# Motor_Board.net
KiCad netlist of a schematic drawn in EAGLE
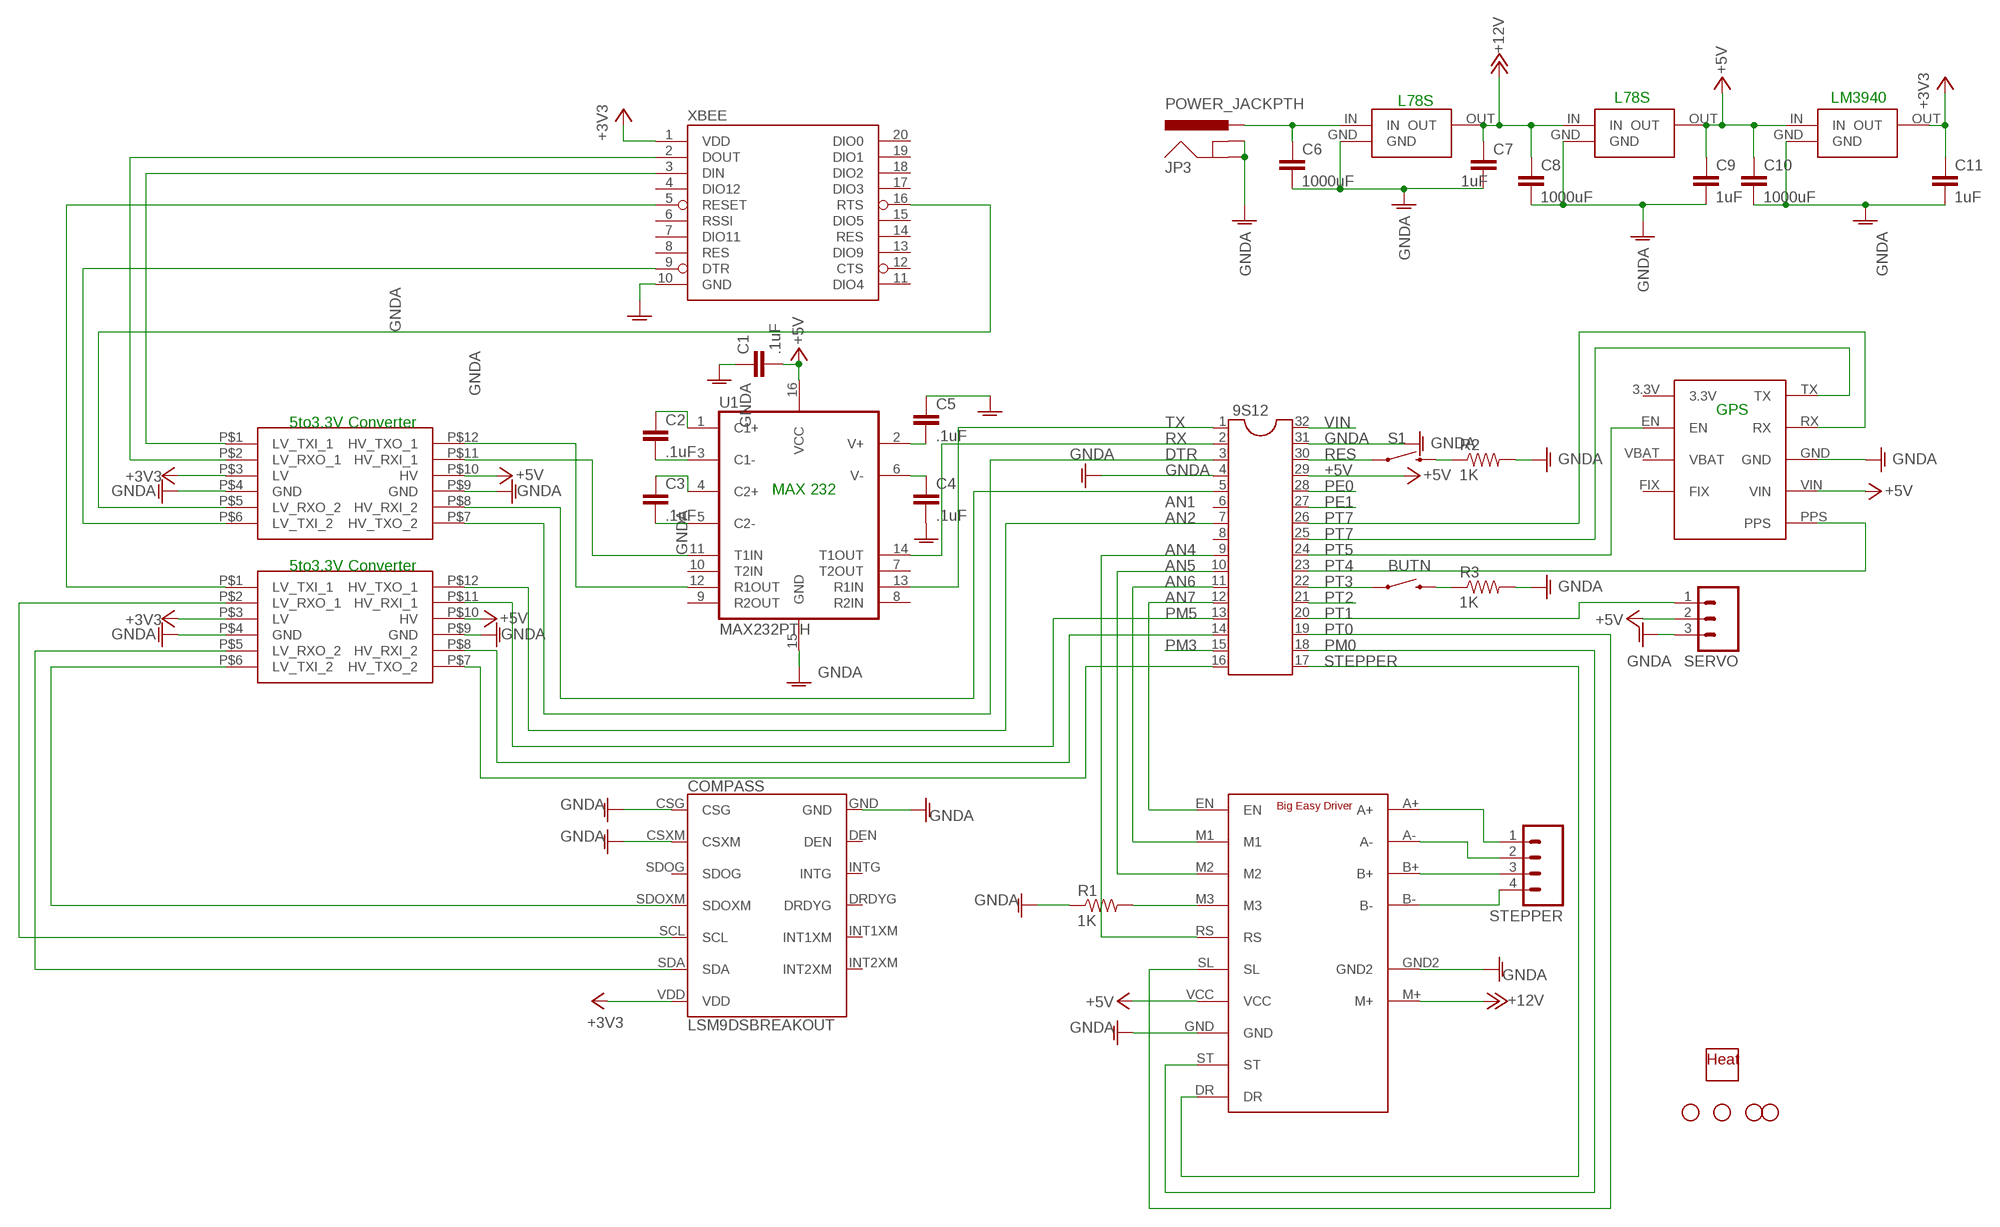
[diagram p0: schematic, sheet 1]

(export (version "E")
  (design (tool "Eeschema 10.0.6"))
  (components
    (comp (ref "9S12")
      (value "DIL32")
      (footprint "eagle-import:DIL32")
      (libsource (lib "eagle-import") (part "DIL32"))
    )
    (comp (ref "BUTN")
      (value "EXTERNALBUTTON")
      (footprint "eagle-import:EXTERNALBUTTON")
      (libsource (lib "eagle-import") (part "EXTERNALBUTTON"))
    )
    (comp (ref "C1")
      (value ".1uF")
      (footprint "eagle-import:CAP-PTH-SMALL")
      (libsource (lib "eagle-import") (part "CAPPTH"))
    )
    (comp (ref "C2")
      (value ".1uF")
      (footprint "eagle-import:CAP-PTH-SMALL")
      (libsource (lib "eagle-import") (part "CAPPTH"))
    )
    (comp (ref "C3")
      (value ".1uF")
      (footprint "eagle-import:CAP-PTH-SMALL")
      (libsource (lib "eagle-import") (part "CAPPTH"))
    )
    (comp (ref "C4")
      (value ".1uF")
      (footprint "eagle-import:CAP-PTH-SMALL")
      (libsource (lib "eagle-import") (part "CAPPTH"))
    )
    (comp (ref "C5")
      (value ".1uF")
      (footprint "eagle-import:CAP-PTH-SMALL")
      (libsource (lib "eagle-import") (part "CAPPTH"))
    )
    (comp (ref "C6")
      (value "1000uF")
      (footprint "eagle-import:CAP")
      (libsource (lib "eagle-import") (part "CAP_2000UF"))
    )
    (comp (ref "C7")
      (value "1uF")
      (footprint "eagle-import:CAP-PTH-SMALL")
      (libsource (lib "eagle-import") (part "CAPPTH"))
    )
    (comp (ref "C8")
      (value "1000uF")
      (footprint "eagle-import:CAP")
      (libsource (lib "eagle-import") (part "CAP_2000UF"))
    )
    (comp (ref "C9")
      (value "1uF")
      (footprint "eagle-import:CAP-PTH-SMALL")
      (libsource (lib "eagle-import") (part "CAPPTH"))
    )
    (comp (ref "C10")
      (value "1000uF")
      (footprint "eagle-import:CAP")
      (libsource (lib "eagle-import") (part "CAP_2000UF"))
    )
    (comp (ref "C11")
      (value "1uF")
      (footprint "eagle-import:CAP-PTH-SMALL")
      (libsource (lib "eagle-import") (part "CAPPTH"))
    )
    (comp (ref "COMPASS")
      (value "LSM9DSBREAKOUT")
      (footprint "eagle-import:IMUBREAKOUT")
      (libsource (lib "eagle-import") (part "LSM9DSBREAKOUT"))
    )
    (comp (ref "JP3")
      (value "POWER_JACKPTH")
      (footprint "eagle-import:POWER_JACK_PTH")
      (libsource (lib "eagle-import") (part "POWER_JACKPTH"))
    )
    (comp (ref "R1")
      (value "1K")
      (footprint "eagle-import:AXIAL-0.4")
      (libsource (lib "eagle-import") (part "RESISTORPTH-1/4W"))
    )
    (comp (ref "R2")
      (value "1K")
      (footprint "eagle-import:AXIAL-0.4")
      (libsource (lib "eagle-import") (part "RESISTORPTH-1/4W"))
    )
    (comp (ref "R3")
      (value "1K")
      (footprint "eagle-import:AXIAL-0.4")
      (libsource (lib "eagle-import") (part "RESISTORPTH-1/4W"))
    )
    (comp (ref "REG_5TO3.3")
      (value "POWERREG_5TO3.3_NOHEAT")
      (footprint "eagle-import:POWERREG_NOHEAT")
      (libsource (lib "eagle-import") (part "POWERREG_5TO3.3_NOHEAT"))
    )
    (comp (ref "REG_12TO5")
      (value "POWERREG_12TO5")
      (footprint "eagle-import:POWERREG")
      (libsource (lib "eagle-import") (part "POWERREG_12TO5"))
    )
    (comp (ref "REG_18TO12")
      (value "POWERREG18VTO12V")
      (footprint "eagle-import:POWERREG")
      (libsource (lib "eagle-import") (part "POWERREG18VTO12V"))
    )
    (comp (ref "S1")
      (value "SWITCH-MOMENTARY-2PTH")
      (footprint "eagle-import:TACTILE-PTH")
      (libsource (lib "eagle-import") (part "SWITCH-MOMENTARY-2PTH"))
    )
    (comp (ref "SERVO")
      (value "M03PTH")
      (footprint "eagle-import:1X03")
      (libsource (lib "eagle-import") (part "M03PTH"))
    )
    (comp (ref "STANDOFF1")
      (value "STAND-OFF")
      (footprint "eagle-import:STAND-OFF")
      (libsource (lib "eagle-import") (part "STAND-OFF"))
    )
    (comp (ref "STANDOFF2")
      (value "STAND-OFF")
      (footprint "eagle-import:STAND-OFF")
      (libsource (lib "eagle-import") (part "STAND-OFF"))
    )
    (comp (ref "STANDOFF3")
      (value "STAND-OFF")
      (footprint "eagle-import:STAND-OFF")
      (libsource (lib "eagle-import") (part "STAND-OFF"))
    )
    (comp (ref "STANDOFF4")
      (value "STAND-OFF")
      (footprint "eagle-import:STAND-OFF")
      (libsource (lib "eagle-import") (part "STAND-OFF"))
    )
    (comp (ref "STEPPER")
      (value "M04NO_SILK_ALL_ROUND")
      (footprint "eagle-import:1X04_NO_SILK_ALL_ROUND")
      (libsource (lib "eagle-import") (part "M04NO_SILK_ALL_ROUND"))
    )
    (comp (ref "U$1")
      (value "5to3.3")
      (footprint "eagle-import:LOGIC_LEVEL_CONVERTER")
      (libsource (lib "eagle-import") (part "LOGIC_LEVEL_CONVERTER"))
    )
    (comp (ref "U$2")
      (value "5to3.3")
      (footprint "eagle-import:LOGIC_LEVEL_CONVERTER")
      (libsource (lib "eagle-import") (part "LOGIC_LEVEL_CONVERTER"))
    )
    (comp (ref "U$3")
      (value "BIGEASYDRIVER")
      (footprint "eagle-import:BIGEASYDRIVER")
      (libsource (lib "eagle-import") (part "BIGEASYDRIVER"))
    )
    (comp (ref "U$4")
      (value "GPS")
      (footprint "eagle-import:GPS")
      (libsource (lib "eagle-import") (part "GPS"))
    )
    (comp (ref "U$9")
      (value "HEATSINK")
      (footprint "eagle-import:HEATSINK")
      (libsource (lib "eagle-import") (part "HEATSINK"))
    )
    (comp (ref "U1")
      (value "MAX232PTH")
      (footprint "eagle-import:DIL16")
      (libsource (lib "eagle-import") (part "MAX232PTH"))
    )
    (comp (ref "XBEE")
      (value "XBEE-1B1")
      (footprint "eagle-import:XBEE-1")
      (libsource (lib "eagle-import") (part "XBEE-1B1"))
    )
  )
  (nets
    (net (code "1") (name "+3V3") (class "Default")
      (node (ref "C11") (pin "1") (pinfunction "1_1") (pintype "passive"))
      (node (ref "COMPASS") (pin "VDD") (pinfunction "VDD_VDD") (pintype "bidirectional"))
      (node (ref "REG_5TO3.3") (pin "OUT") (pinfunction "OUT_OUT") (pintype "bidirectional"))
      (node (ref "U$1") (pin "P$3") (pinfunction "LV_P$3") (pintype "bidirectional"))
      (node (ref "U$2") (pin "P$3") (pinfunction "LV_P$3") (pintype "bidirectional"))
      (node (ref "XBEE") (pin "1") (pinfunction "VDD_1") (pintype "power_in"))
    )
    (net (code "2") (name "+5V") (class "Default")
      (node (ref "9S12") (pin "29") (pinfunction "29_29") (pintype "passive"))
      (node (ref "C1") (pin "2") (pinfunction "2_2") (pintype "passive"))
      (node (ref "C10") (pin "1") (pinfunction "1_1") (pintype "passive"))
      (node (ref "C9") (pin "1") (pinfunction "1_1") (pintype "passive"))
      (node (ref "REG_12TO5") (pin "OUT") (pinfunction "OUT_OUT") (pintype "bidirectional"))
      (node (ref "REG_5TO3.3") (pin "IN") (pinfunction "IN_IN") (pintype "bidirectional"))
      (node (ref "SERVO") (pin "2") (pinfunction "2_2") (pintype "passive"))
      (node (ref "U$1") (pin "P$10") (pinfunction "HV_P$10") (pintype "bidirectional"))
      (node (ref "U$2") (pin "P$10") (pinfunction "HV_P$10") (pintype "bidirectional"))
      (node (ref "U$3") (pin "VCC") (pinfunction "VCC_VCC") (pintype "bidirectional"))
      (node (ref "U$4") (pin "VIN") (pinfunction "VIN_VIN") (pintype "bidirectional"))
      (node (ref "U1") (pin "16") (pinfunction "VCC_16") (pintype "bidirectional"))
    )
    (net (code "3") (name "+12V") (class "Default")
      (node (ref "C7") (pin "1") (pinfunction "1_1") (pintype "passive"))
      (node (ref "C8") (pin "1") (pinfunction "1_1") (pintype "passive"))
      (node (ref "REG_12TO5") (pin "IN") (pinfunction "IN_IN") (pintype "bidirectional"))
      (node (ref "REG_18TO12") (pin "OUT") (pinfunction "OUT_OUT") (pintype "bidirectional"))
      (node (ref "U$3") (pin "M+") (pinfunction "M+_M+") (pintype "bidirectional"))
    )
    (net (code "4") (name "/AN1") (class "Default")
      (node (ref "U$2") (pin "P$6") (pinfunction "LV_TXI_2_P$6") (pintype "bidirectional"))
      (node (ref "XBEE") (pin "9") (pinfunction "DTR_9") (pintype "bidirectional"))
    )
    (net (code "5") (name "/AN2") (class "Default")
      (node (ref "U$1") (pin "P$1") (pinfunction "LV_TXI_1_P$1") (pintype "bidirectional"))
      (node (ref "XBEE") (pin "5") (pinfunction "RESET_5") (pintype "input"))
    )
    (net (code "6") (name "/AN4") (class "Default")
      (node (ref "9S12") (pin "9") (pinfunction "9_9") (pintype "passive"))
      (node (ref "U$3") (pin "RS") (pinfunction "RS_RS") (pintype "bidirectional"))
    )
    (net (code "7") (name "/AN5") (class "Default")
      (node (ref "9S12") (pin "10") (pinfunction "10_10") (pintype "passive"))
      (node (ref "U$3") (pin "M2") (pinfunction "M2_M2") (pintype "bidirectional"))
    )
    (net (code "8") (name "/AN6") (class "Default")
      (node (ref "9S12") (pin "11") (pinfunction "11_11") (pintype "passive"))
      (node (ref "U$3") (pin "M1") (pinfunction "M1_M1") (pintype "bidirectional"))
    )
    (net (code "9") (name "/AN7") (class "Default")
      (node (ref "9S12") (pin "12") (pinfunction "12_12") (pintype "passive"))
      (node (ref "U$3") (pin "EN") (pinfunction "EN_EN") (pintype "bidirectional"))
    )
    (net (code "10") (name "/DTR") (class "Default")
      (node (ref "9S12") (pin "3") (pinfunction "3_3") (pintype "passive"))
      (node (ref "U$2") (pin "P$7") (pinfunction "HV_TXO_2_P$7") (pintype "bidirectional"))
    )
    (net (code "11") (name "/PE0") (class "Default")
      (node (ref "9S12") (pin "28") (pinfunction "28_28") (pintype "passive"))
    )
    (net (code "12") (name "/PE1") (class "Default")
      (node (ref "9S12") (pin "27") (pinfunction "27_27") (pintype "passive"))
    )
    (net (code "13") (name "/PM0") (class "Default")
      (node (ref "9S12") (pin "18") (pinfunction "18_18") (pintype "passive"))
      (node (ref "U$3") (pin "ST") (pinfunction "ST_ST") (pintype "bidirectional"))
    )
    (net (code "14") (name "/PM3") (class "Default")
      (node (ref "9S12") (pin "15") (pinfunction "15_15") (pintype "passive"))
    )
    (net (code "15") (name "/PM5") (class "Default")
      (node (ref "9S12") (pin "13") (pinfunction "13_13") (pintype "passive"))
      (node (ref "U$1") (pin "P$11") (pinfunction "HV_RXI_1_P$11") (pintype "bidirectional"))
    )
    (net (code "16") (name "/PT0") (class "Default")
      (node (ref "9S12") (pin "19") (pinfunction "19_19") (pintype "passive"))
      (node (ref "U$3") (pin "SL") (pinfunction "SL_SL") (pintype "bidirectional"))
    )
    (net (code "17") (name "/PT1") (class "Default")
      (node (ref "9S12") (pin "20") (pinfunction "20_20") (pintype "passive"))
      (node (ref "SERVO") (pin "1") (pinfunction "1_1") (pintype "passive"))
    )
    (net (code "18") (name "/PT2") (class "Default")
      (node (ref "9S12") (pin "21") (pinfunction "21_21") (pintype "passive"))
    )
    (net (code "19") (name "/PT3") (class "Default")
      (node (ref "9S12") (pin "22") (pinfunction "22_22") (pintype "passive"))
      (node (ref "BUTN") (pin "1") (pinfunction "1_1") (pintype "passive"))
    )
    (net (code "20") (name "/PT4") (class "Default")
      (node (ref "9S12") (pin "23") (pinfunction "23_23") (pintype "passive"))
      (node (ref "U$4") (pin "PPS") (pinfunction "PPS_PPS") (pintype "bidirectional"))
    )
    (net (code "21") (name "/PT5") (class "Default")
      (node (ref "9S12") (pin "24") (pinfunction "24_24") (pintype "passive"))
      (node (ref "U$4") (pin "EN") (pinfunction "EN_EN") (pintype "bidirectional"))
    )
    (net (code "22") (name "/PT7") (class "Default")
      (node (ref "9S12") (pin "26") (pinfunction "26_26") (pintype "passive"))
      (node (ref "U$4") (pin "RX") (pinfunction "RX_RX") (pintype "bidirectional"))
    )
    (net (code "23") (name "/RES") (class "Default")
      (node (ref "9S12") (pin "30") (pinfunction "30_30") (pintype "passive"))
      (node (ref "S1") (pin "1") (pinfunction "1_1") (pintype "passive"))
    )
    (net (code "24") (name "/RX") (class "Default")
      (node (ref "U$2") (pin "P$2") (pinfunction "LV_RXO_1_P$2") (pintype "bidirectional"))
      (node (ref "XBEE") (pin "2") (pinfunction "DOUT_2") (pintype "output"))
    )
    (net (code "25") (name "/STEPPER") (class "Default")
      (node (ref "9S12") (pin "17") (pinfunction "17_17") (pintype "passive"))
      (node (ref "U$3") (pin "DR") (pinfunction "DR_DR") (pintype "bidirectional"))
    )
    (net (code "26") (name "/TX") (class "Default")
      (node (ref "U$2") (pin "P$1") (pinfunction "LV_TXI_1_P$1") (pintype "bidirectional"))
      (node (ref "XBEE") (pin "3") (pinfunction "DIN_3") (pintype "input"))
    )
    (net (code "27") (name "/VIN") (class "Default")
      (node (ref "9S12") (pin "32") (pinfunction "32_32") (pintype "passive"))
    )
    (net (code "28") (name "GNDA") (class "Default")
      (node (ref "9S12") (pin "31") (pinfunction "31_31") (pintype "passive"))
      (node (ref "9S12") (pin "4") (pinfunction "4_4") (pintype "passive"))
      (node (ref "C1") (pin "1") (pinfunction "1_1") (pintype "passive"))
      (node (ref "C10") (pin "2") (pinfunction "2_2") (pintype "passive"))
      (node (ref "C11") (pin "2") (pinfunction "2_2") (pintype "passive"))
      (node (ref "C4") (pin "2") (pinfunction "2_2") (pintype "passive"))
      (node (ref "C5") (pin "1") (pinfunction "1_1") (pintype "passive"))
      (node (ref "C6") (pin "2") (pinfunction "2_2") (pintype "passive"))
      (node (ref "C7") (pin "2") (pinfunction "2_2") (pintype "passive"))
      (node (ref "C8") (pin "2") (pinfunction "2_2") (pintype "passive"))
      (node (ref "C9") (pin "2") (pinfunction "2_2") (pintype "passive"))
      (node (ref "COMPASS") (pin "CSG") (pinfunction "CSG_CSG") (pintype "bidirectional"))
      (node (ref "COMPASS") (pin "CSXM") (pinfunction "CSXM_CSXM") (pintype "bidirectional"))
      (node (ref "COMPASS") (pin "GND") (pinfunction "GND_GND") (pintype "bidirectional"))
      (node (ref "JP3") (pin "GND") (pinfunction "GND_GND") (pintype "bidirectional"))
      (node (ref "JP3") (pin "GNDBREAK") (pinfunction "GNDBREAK_GNDBREAK") (pintype "bidirectional"))
      (node (ref "R1") (pin "P$1") (pinfunction "1_P$1") (pintype "passive"))
      (node (ref "R2") (pin "P$2") (pinfunction "2_P$2") (pintype "passive"))
      (node (ref "R3") (pin "P$2") (pinfunction "2_P$2") (pintype "passive"))
      (node (ref "REG_12TO5") (pin "GND") (pinfunction "GND_GND") (pintype "bidirectional"))
      (node (ref "REG_18TO12") (pin "GND") (pinfunction "GND_GND") (pintype "bidirectional"))
      (node (ref "REG_5TO3.3") (pin "GND") (pinfunction "GND_GND") (pintype "bidirectional"))
      (node (ref "SERVO") (pin "3") (pinfunction "3_3") (pintype "passive"))
      (node (ref "U$1") (pin "P$4") (pinfunction "GND_P$4") (pintype "bidirectional"))
      (node (ref "U$1") (pin "P$9") (pinfunction "GND_P$9") (pintype "bidirectional"))
      (node (ref "U$2") (pin "P$4") (pinfunction "GND_P$4") (pintype "bidirectional"))
      (node (ref "U$2") (pin "P$9") (pinfunction "GND_P$9") (pintype "bidirectional"))
      (node (ref "U$3") (pin "GND") (pinfunction "GND_GND") (pintype "bidirectional"))
      (node (ref "U$3") (pin "GND2") (pinfunction "GND2_GND2") (pintype "bidirectional"))
      (node (ref "U$4") (pin "GND") (pinfunction "GND_GND") (pintype "bidirectional"))
      (node (ref "U1") (pin "15") (pinfunction "GND_15") (pintype "bidirectional"))
      (node (ref "XBEE") (pin "10") (pinfunction "GND_10") (pintype "power_in"))
    )
    (net (code "29") (name "Net-(9S12-Pad25)") (class "Default")
      (node (ref "9S12") (pin "25") (pinfunction "25_25") (pintype "passive"))
      (node (ref "U$4") (pin "TX") (pinfunction "TX_TX") (pintype "bidirectional"))
    )
    (net (code "30") (name "Net-(C6-Pad1)") (class "Default")
      (node (ref "C6") (pin "1") (pinfunction "1_1") (pintype "passive"))
      (node (ref "JP3") (pin "PWR") (pinfunction "PWR_PWR") (pintype "bidirectional"))
      (node (ref "REG_18TO12") (pin "IN") (pinfunction "IN_IN") (pintype "bidirectional"))
    )
    (net (code "31") (name "Net-(R1-2)") (class "Default")
      (node (ref "R1") (pin "P$2") (pinfunction "2_P$2") (pintype "passive"))
      (node (ref "U$3") (pin "M3") (pinfunction "M3_M3") (pintype "bidirectional"))
    )
    (net (code "32") (name "Net-(R2-1)") (class "Default")
      (node (ref "R2") (pin "P$1") (pinfunction "1_P$1") (pintype "passive"))
      (node (ref "S1") (pin "3") (pinfunction "2_3") (pintype "passive"))
    )
    (net (code "33") (name "Net-(R3-1)") (class "Default")
      (node (ref "BUTN") (pin "2") (pinfunction "2_2") (pintype "passive"))
      (node (ref "R3") (pin "P$1") (pinfunction "1_P$1") (pintype "passive"))
    )
    (net (code "34") (name "Net-(STEPPER-Pad1)") (class "Default")
      (node (ref "STEPPER") (pin "1") (pinfunction "1_1") (pintype "passive"))
      (node (ref "U$3") (pin "A+") (pinfunction "A+_A+") (pintype "bidirectional"))
    )
    (net (code "35") (name "Net-(STEPPER-Pad2)") (class "Default")
      (node (ref "STEPPER") (pin "2") (pinfunction "2_2") (pintype "passive"))
      (node (ref "U$3") (pin "A-") (pinfunction "A-_A-") (pintype "bidirectional"))
    )
    (net (code "36") (name "Net-(STEPPER-Pad3)") (class "Default")
      (node (ref "STEPPER") (pin "3") (pinfunction "3_3") (pintype "passive"))
      (node (ref "U$3") (pin "B+") (pinfunction "B+_B+") (pintype "bidirectional"))
    )
    (net (code "37") (name "Net-(STEPPER-Pad4)") (class "Default")
      (node (ref "STEPPER") (pin "4") (pinfunction "4_4") (pintype "passive"))
      (node (ref "U$3") (pin "B-") (pinfunction "B-_B-") (pintype "bidirectional"))
    )
    (net (code "38") (name "Net-(U$1-HV_RXI_2)") (class "Default")
      (node (ref "9S12") (pin "14") (pinfunction "14_14") (pintype "passive"))
      (node (ref "U$1") (pin "P$8") (pinfunction "HV_RXI_2_P$8") (pintype "bidirectional"))
    )
    (net (code "39") (name "Net-(U$1-HV_TXO_1)") (class "Default")
      (node (ref "9S12") (pin "7") (pinfunction "7_7") (pintype "passive"))
      (node (ref "U$1") (pin "P$12") (pinfunction "HV_TXO_1_P$12") (pintype "bidirectional"))
    )
    (net (code "40") (name "Net-(U$1-HV_TXO_2)") (class "Default")
      (node (ref "9S12") (pin "16") (pinfunction "16_16") (pintype "passive"))
      (node (ref "U$1") (pin "P$7") (pinfunction "HV_TXO_2_P$7") (pintype "bidirectional"))
    )
    (net (code "41") (name "Net-(U$1-LV_RXO_1)") (class "Default")
      (node (ref "COMPASS") (pin "SCL") (pinfunction "SCL_SCL") (pintype "bidirectional"))
      (node (ref "U$1") (pin "P$2") (pinfunction "LV_RXO_1_P$2") (pintype "bidirectional"))
    )
    (net (code "42") (name "Net-(U$1-LV_RXO_2)") (class "Default")
      (node (ref "COMPASS") (pin "SDA") (pinfunction "SDA_SDA") (pintype "bidirectional"))
      (node (ref "U$1") (pin "P$5") (pinfunction "LV_RXO_2_P$5") (pintype "bidirectional"))
    )
    (net (code "43") (name "Net-(U$1-LV_TXI_2)") (class "Default")
      (node (ref "COMPASS") (pin "SDOXM") (pinfunction "SDOXM_SDOXM") (pintype "bidirectional"))
      (node (ref "U$1") (pin "P$6") (pinfunction "LV_TXI_2_P$6") (pintype "bidirectional"))
    )
    (net (code "44") (name "Net-(U$2-HV_RXI_1)") (class "Default")
      (node (ref "U$2") (pin "P$11") (pinfunction "HV_RXI_1_P$11") (pintype "bidirectional"))
      (node (ref "U1") (pin "11") (pinfunction "T1IN_11") (pintype "input"))
    )
    (net (code "45") (name "Net-(U$2-HV_RXI_2)") (class "Default")
      (node (ref "9S12") (pin "5") (pinfunction "5_5") (pintype "passive"))
      (node (ref "U$2") (pin "P$8") (pinfunction "HV_RXI_2_P$8") (pintype "bidirectional"))
    )
    (net (code "46") (name "Net-(U$2-HV_TXO_1)") (class "Default")
      (node (ref "U$2") (pin "P$12") (pinfunction "HV_TXO_1_P$12") (pintype "bidirectional"))
      (node (ref "U1") (pin "12") (pinfunction "R1OUT_12") (pintype "output"))
    )
    (net (code "47") (name "Net-(U$2-LV_RXO_2)") (class "Default")
      (node (ref "U$2") (pin "P$5") (pinfunction "LV_RXO_2_P$5") (pintype "bidirectional"))
      (node (ref "XBEE") (pin "16") (pinfunction "RTS_16") (pintype "input"))
    )
    (net (code "48") (name "Net-(U1-C1+)") (class "Default")
      (node (ref "C2") (pin "1") (pinfunction "1_1") (pintype "passive"))
      (node (ref "U1") (pin "1") (pinfunction "C1+_1") (pintype "bidirectional"))
    )
    (net (code "49") (name "Net-(U1-C1-)") (class "Default")
      (node (ref "C2") (pin "2") (pinfunction "2_2") (pintype "passive"))
      (node (ref "U1") (pin "3") (pinfunction "C1-_3") (pintype "bidirectional"))
    )
    (net (code "50") (name "Net-(U1-C2+)") (class "Default")
      (node (ref "C3") (pin "1") (pinfunction "1_1") (pintype "passive"))
      (node (ref "U1") (pin "4") (pinfunction "C2+_4") (pintype "bidirectional"))
    )
    (net (code "51") (name "Net-(U1-C2-)") (class "Default")
      (node (ref "C3") (pin "2") (pinfunction "2_2") (pintype "passive"))
      (node (ref "U1") (pin "5") (pinfunction "C2-_5") (pintype "bidirectional"))
    )
    (net (code "52") (name "Net-(U1-R1IN)") (class "Default")
      (node (ref "9S12") (pin "1") (pinfunction "1_1") (pintype "passive"))
      (node (ref "U1") (pin "13") (pinfunction "R1IN_13") (pintype "input"))
    )
    (net (code "53") (name "Net-(U1-T1OUT)") (class "Default")
      (node (ref "9S12") (pin "2") (pinfunction "2_2") (pintype "passive"))
      (node (ref "U1") (pin "14") (pinfunction "T1OUT_14") (pintype "output"))
    )
    (net (code "54") (name "Net-(U1-V+)") (class "Default")
      (node (ref "C5") (pin "2") (pinfunction "2_2") (pintype "passive"))
      (node (ref "U1") (pin "2") (pinfunction "V+_2") (pintype "bidirectional"))
    )
    (net (code "55") (name "Net-(U1-V-)") (class "Default")
      (node (ref "C4") (pin "1") (pinfunction "1_1") (pintype "passive"))
      (node (ref "U1") (pin "6") (pinfunction "V-_6") (pintype "bidirectional"))
    )
    (net (code "56") (name "unconnected-(9S12-Pad6)") (class "Default")
      (node (ref "9S12") (pin "6") (pinfunction "6_6") (pintype "passive"))
    )
    (net (code "57") (name "unconnected-(9S12-Pad8)") (class "Default")
      (node (ref "9S12") (pin "8") (pinfunction "8_8") (pintype "passive"))
    )
    (net (code "58") (name "unconnected-(COMPASS-PadDEN)") (class "Default")
      (node (ref "COMPASS") (pin "DEN") (pinfunction "DEN_DEN") (pintype "bidirectional"))
    )
    (net (code "59") (name "unconnected-(COMPASS-PadDRDYG)") (class "Default")
      (node (ref "COMPASS") (pin "DRDYG") (pinfunction "DRDYG_DRDYG") (pintype "bidirectional"))
    )
    (net (code "60") (name "unconnected-(COMPASS-PadINT1XM)") (class "Default")
      (node (ref "COMPASS") (pin "INT1XM") (pinfunction "INT1XM_INT1XM") (pintype "bidirectional"))
    )
    (net (code "61") (name "unconnected-(COMPASS-PadINT2XM)") (class "Default")
      (node (ref "COMPASS") (pin "INT2XM") (pinfunction "INT2XM_INT2XM") (pintype "bidirectional"))
    )
    (net (code "62") (name "unconnected-(COMPASS-PadINTG)") (class "Default")
      (node (ref "COMPASS") (pin "INTG") (pinfunction "INTG_INTG") (pintype "bidirectional"))
    )
    (net (code "63") (name "unconnected-(COMPASS-PadSDOG)") (class "Default")
      (node (ref "COMPASS") (pin "SDOG") (pinfunction "SDOG_SDOG") (pintype "bidirectional"))
    )
    (net (code "64") (name "unconnected-(U$4-Pad3.3V)") (class "Default")
      (node (ref "U$4") (pin "3.3V") (pinfunction "3.3V_3.3V") (pintype "bidirectional"))
    )
    (net (code "65") (name "unconnected-(U$4-PadFIX)") (class "Default")
      (node (ref "U$4") (pin "FIX") (pinfunction "FIX_FIX") (pintype "bidirectional"))
    )
    (net (code "66") (name "unconnected-(U$4-PadVBAT)") (class "Default")
      (node (ref "U$4") (pin "VBAT") (pinfunction "VBAT_VBAT") (pintype "bidirectional"))
    )
    (net (code "67") (name "unconnected-(U1-R2IN-Pad8)") (class "Default")
      (node (ref "U1") (pin "8") (pinfunction "R2IN_8") (pintype "input"))
    )
    (net (code "68") (name "unconnected-(U1-R2OUT-Pad9)") (class "Default")
      (node (ref "U1") (pin "9") (pinfunction "R2OUT_9") (pintype "output"))
    )
    (net (code "69") (name "unconnected-(U1-T2IN-Pad10)") (class "Default")
      (node (ref "U1") (pin "10") (pinfunction "T2IN_10") (pintype "input"))
    )
    (net (code "70") (name "unconnected-(U1-T2OUT-Pad7)") (class "Default")
      (node (ref "U1") (pin "7") (pinfunction "T2OUT_7") (pintype "output"))
    )
    (net (code "71") (name "unconnected-(XBEE-CTS-Pad12)") (class "Default")
      (node (ref "XBEE") (pin "12") (pinfunction "CTS_12") (pintype "output"))
    )
    (net (code "72") (name "unconnected-(XBEE-DIO0-Pad20)") (class "Default")
      (node (ref "XBEE") (pin "20") (pinfunction "DIO0_20") (pintype "bidirectional"))
    )
    (net (code "73") (name "unconnected-(XBEE-DIO1-Pad19)") (class "Default")
      (node (ref "XBEE") (pin "19") (pinfunction "DIO1_19") (pintype "bidirectional"))
    )
    (net (code "74") (name "unconnected-(XBEE-DIO2-Pad18)") (class "Default")
      (node (ref "XBEE") (pin "18") (pinfunction "DIO2_18") (pintype "bidirectional"))
    )
    (net (code "75") (name "unconnected-(XBEE-DIO3-Pad17)") (class "Default")
      (node (ref "XBEE") (pin "17") (pinfunction "DIO3_17") (pintype "bidirectional"))
    )
    (net (code "76") (name "unconnected-(XBEE-DIO4-Pad11)") (class "Default")
      (node (ref "XBEE") (pin "11") (pinfunction "DIO4_11") (pintype "bidirectional"))
    )
    (net (code "77") (name "unconnected-(XBEE-DIO5-Pad15)") (class "Default")
      (node (ref "XBEE") (pin "15") (pinfunction "DIO5_15") (pintype "bidirectional"))
    )
    (net (code "78") (name "unconnected-(XBEE-DIO9-Pad13)") (class "Default")
      (node (ref "XBEE") (pin "13") (pinfunction "DIO9_13") (pintype "bidirectional"))
    )
    (net (code "79") (name "unconnected-(XBEE-DIO11-Pad7)") (class "Default")
      (node (ref "XBEE") (pin "7") (pinfunction "DIO11_7") (pintype "bidirectional"))
    )
    (net (code "80") (name "unconnected-(XBEE-DIO12-Pad4)") (class "Default")
      (node (ref "XBEE") (pin "4") (pinfunction "DIO12_4") (pintype "bidirectional"))
    )
    (net (code "81") (name "unconnected-(XBEE-RES-Pad8)") (class "Default")
      (node (ref "XBEE") (pin "8") (pinfunction "RES_8") (pintype "bidirectional"))
    )
    (net (code "82") (name "unconnected-(XBEE-RES-Pad14)") (class "Default")
      (node (ref "XBEE") (pin "14") (pinfunction "RES_14") (pintype "bidirectional"))
    )
    (net (code "83") (name "unconnected-(XBEE-RSSI-Pad6)") (class "Default")
      (node (ref "XBEE") (pin "6") (pinfunction "RSSI_6") (pintype "bidirectional"))
    )
  )
)
